# Planck-HUB.net
KiCad netlist of a schematic drawn in Altium Designer
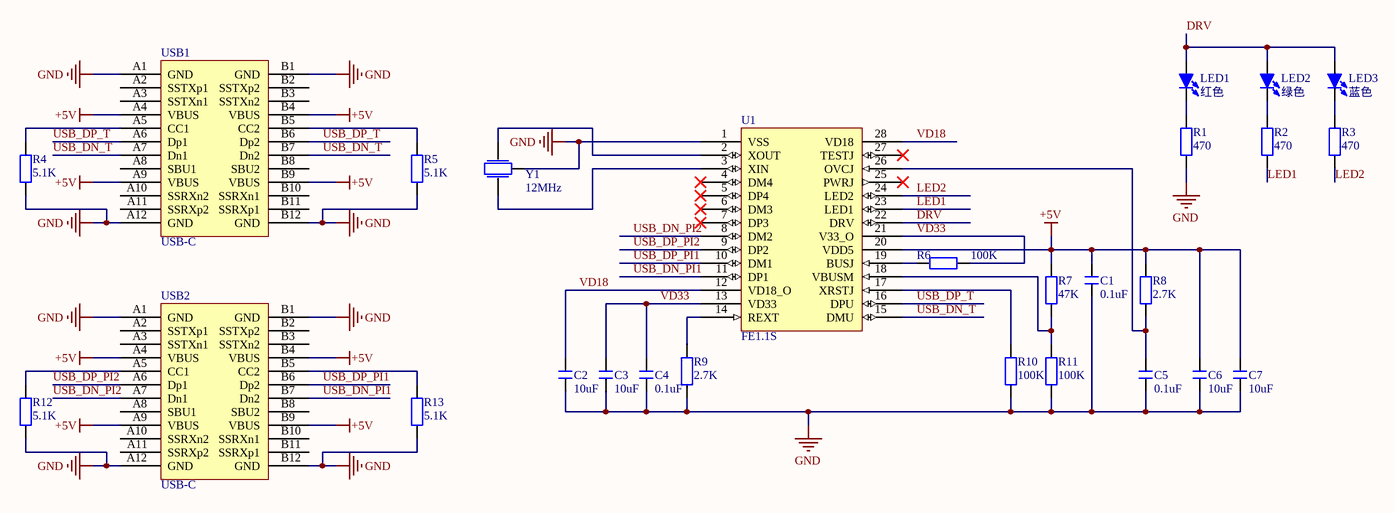
[diagram p0: Planck-HUB.SchDoc]

(export (version "E")
  (design (tool "Eeschema 10.0.6"))
  (components
    (comp (ref "C1")
      (value "0.1uF")
      (footprint "C 0402_L")
      (description "贴片电容")
      (libsource (lib "0.1 - 电阻-电容-电感") (part "C"))
    )
    (comp (ref "C2")
      (value "10uF")
      (footprint "C 0402_L")
      (description "贴片电容")
      (libsource (lib "0.1 - 电阻-电容-电感") (part "C"))
    )
    (comp (ref "C3")
      (value "10uF")
      (footprint "C 0402_L")
      (description "贴片电容")
      (libsource (lib "0.1 - 电阻-电容-电感") (part "C"))
    )
    (comp (ref "C4")
      (value "0.1uF")
      (footprint "C 0402_L")
      (description "贴片电容")
      (libsource (lib "0.1 - 电阻-电容-电感") (part "C"))
    )
    (comp (ref "C5")
      (value "0.1uF")
      (footprint "C 0402_L")
      (description "贴片电容")
      (libsource (lib "0.1 - 电阻-电容-电感") (part "C"))
    )
    (comp (ref "C6")
      (value "10uF")
      (footprint "C 0402_L")
      (description "贴片电容")
      (libsource (lib "0.1 - 电阻-电容-电感") (part "C"))
    )
    (comp (ref "C7")
      (value "10uF")
      (footprint "C 0402_L")
      (description "贴片电容")
      (libsource (lib "0.1 - 电阻-电容-电感") (part "C"))
    )
    (comp (ref "LED1")
      (value "红色")
      (footprint "LED_0402_RED")
      (description "贴片LED")
      (fields (field (name "版权归属") "封装库来自淘宝 ID：黄晶宝石"))
      (libsource (lib "0.3 - LED发光二极管") (part "LED-SMD"))
    )
    (comp (ref "LED2")
      (value "绿色")
      (footprint "LED_0402_RED")
      (description "贴片LED")
      (fields (field (name "版权归属") "封装库来自淘宝 ID：黄晶宝石"))
      (libsource (lib "0.3 - LED发光二极管") (part "LED-SMD"))
    )
    (comp (ref "LED3")
      (value "蓝色")
      (footprint "LED_0402_RED")
      (description "贴片LED")
      (fields (field (name "版权归属") "封装库来自淘宝 ID：黄晶宝石"))
      (libsource (lib "0.3 - LED发光二极管") (part "LED-SMD"))
    )
    (comp (ref "R1")
      (value "470")
      (footprint "R 0402_L")
      (description "贴片电阻")
      (fields (field (name "版权归属") "来自淘宝 ID：黄晶宝石"))
      (libsource (lib "0.1 - 电阻-电容-电感") (part "R"))
    )
    (comp (ref "R2")
      (value "470")
      (footprint "R 0402_L")
      (description "贴片电阻")
      (fields (field (name "版权归属") "来自淘宝 ID：黄晶宝石"))
      (libsource (lib "0.1 - 电阻-电容-电感") (part "R"))
    )
    (comp (ref "R3")
      (value "470")
      (footprint "R 0402_L")
      (description "贴片电阻")
      (fields (field (name "版权归属") "来自淘宝 ID：黄晶宝石"))
      (libsource (lib "0.1 - 电阻-电容-电感") (part "R"))
    )
    (comp (ref "R4")
      (value "5.1K")
      (footprint "R 0402_L")
      (description "贴片电阻")
      (fields (field (name "版权归属") "来自淘宝 ID：黄晶宝石"))
      (libsource (lib "0.1 - 电阻-电容-电感") (part "R"))
    )
    (comp (ref "R5")
      (value "5.1K")
      (footprint "R 0402_L")
      (description "贴片电阻")
      (fields (field (name "版权归属") "来自淘宝 ID：黄晶宝石"))
      (libsource (lib "0.1 - 电阻-电容-电感") (part "R"))
    )
    (comp (ref "R6")
      (value "100K")
      (footprint "R 0402_L")
      (description "贴片电阻")
      (fields (field (name "版权归属") "来自淘宝 ID：黄晶宝石"))
      (libsource (lib "0.1 - 电阻-电容-电感") (part "R"))
    )
    (comp (ref "R7")
      (value "47K")
      (footprint "R 0402_L")
      (description "贴片电阻")
      (fields (field (name "版权归属") "来自淘宝 ID：黄晶宝石"))
      (libsource (lib "0.1 - 电阻-电容-电感") (part "R"))
    )
    (comp (ref "R8")
      (value "2.7K")
      (footprint "R 0402_L")
      (description "贴片电阻")
      (fields (field (name "版权归属") "来自淘宝 ID：黄晶宝石"))
      (libsource (lib "0.1 - 电阻-电容-电感") (part "R"))
    )
    (comp (ref "R9")
      (value "2.7K")
      (footprint "R 0402_L")
      (description "贴片电阻")
      (fields (field (name "版权归属") "来自淘宝 ID：黄晶宝石"))
      (libsource (lib "0.1 - 电阻-电容-电感") (part "R"))
    )
    (comp (ref "R10")
      (value "100K")
      (footprint "R 0402_L")
      (description "贴片电阻")
      (fields (field (name "版权归属") "来自淘宝 ID：黄晶宝石"))
      (libsource (lib "0.1 - 电阻-电容-电感") (part "R"))
    )
    (comp (ref "R11")
      (value "100K")
      (footprint "R 0402_L")
      (description "贴片电阻")
      (fields (field (name "版权归属") "来自淘宝 ID：黄晶宝石"))
      (libsource (lib "0.1 - 电阻-电容-电感") (part "R"))
    )
    (comp (ref "R12")
      (value "5.1K")
      (footprint "R 0402_L")
      (description "贴片电阻")
      (fields (field (name "版权归属") "来自淘宝 ID：黄晶宝石"))
      (libsource (lib "0.1 - 电阻-电容-电感") (part "R"))
    )
    (comp (ref "R13")
      (value "5.1K")
      (footprint "R 0402_L")
      (description "贴片电阻")
      (fields (field (name "版权归属") "来自淘宝 ID：黄晶宝石"))
      (libsource (lib "0.1 - 电阻-电容-电感") (part "R"))
    )
    (comp (ref "U1")
      (value "FE1.1S")
      (footprint "SSOP28_L")
      (libsource (lib "自己建的库") (part "FE1.1S USB HUB"))
    )
    (comp (ref "USB1")
      (value "USB-C")
      (footprint "USB Type-C-16Pin_A")
      (description "USB-C型母接口")
      (fields (field (name "版权归属") "源创客"))
      (libsource (lib "接口类") (part "USB-C/S"))
    )
    (comp (ref "USB2")
      (value "USB-C")
      (footprint "USB-C-SMD_TYPE-C-31-G-01")
      (description "USB-C型母接口")
      (fields (field (name "版权归属") "源创客"))
      (libsource (lib "接口类") (part "USB-C/S"))
    )
    (comp (ref "Y1")
      (value "12MHz")
      (footprint "晶振-3P")
      (description "村田贴片")
      (libsource (lib "MyPcbLib") (part "晶振-3Pin"))
    )
  )
  (nets
    (net (code "1") (name "+5V") (class "Default")
      (node (ref "C1") (pin "2") (pinfunction "2_2") (pintype "passive"))
      (node (ref "C6") (pin "2") (pinfunction "2_2") (pintype "passive"))
      (node (ref "C7") (pin "2") (pinfunction "2_2") (pintype "passive"))
      (node (ref "R7") (pin "1") (pinfunction "1_1") (pintype "passive"))
      (node (ref "R8") (pin "1") (pinfunction "1_1") (pintype "passive"))
      (node (ref "U1") (pin "20") (pinfunction "VDD5_20") (pintype "power_in"))
      (node (ref "USB1") (pin "A4") (pinfunction "VBUS_A4") (pintype "passive"))
      (node (ref "USB1") (pin "A9") (pinfunction "VBUS_A9") (pintype "passive"))
      (node (ref "USB1") (pin "B4") (pinfunction "VBUS_B4") (pintype "passive"))
      (node (ref "USB1") (pin "B9") (pinfunction "VBUS_B9") (pintype "passive"))
      (node (ref "USB2") (pin "A4") (pinfunction "VBUS_A4") (pintype "passive"))
      (node (ref "USB2") (pin "A9") (pinfunction "VBUS_A9") (pintype "passive"))
      (node (ref "USB2") (pin "B4") (pinfunction "VBUS_B4") (pintype "passive"))
      (node (ref "USB2") (pin "B9") (pinfunction "VBUS_B9") (pintype "passive"))
    )
    (net (code "2") (name "/DRV") (class "Default")
      (node (ref "LED1") (pin "1") (pinfunction "A_1") (pintype "passive"))
      (node (ref "LED2") (pin "1") (pinfunction "A_1") (pintype "passive"))
      (node (ref "LED3") (pin "1") (pinfunction "A_1") (pintype "passive"))
      (node (ref "U1") (pin "22") (pinfunction "DRV_22") (pintype "bidirectional"))
    )
    (net (code "3") (name "/LED1") (class "Default")
      (node (ref "R2") (pin "1") (pinfunction "1_1") (pintype "passive"))
      (node (ref "U1") (pin "23") (pinfunction "LED1_23") (pintype "bidirectional"))
    )
    (net (code "4") (name "/LED2") (class "Default")
      (node (ref "R3") (pin "1") (pinfunction "1_1") (pintype "passive"))
      (node (ref "U1") (pin "24") (pinfunction "LED2_24") (pintype "bidirectional"))
    )
    (net (code "5") (name "/USB_DN_PI1") (class "Default")
      (node (ref "U1") (pin "11") (pinfunction "DP1_11") (pintype "bidirectional"))
      (node (ref "USB2") (pin "B7") (pinfunction "Dn2_B7") (pintype "passive"))
    )
    (net (code "6") (name "/USB_DN_PI2") (class "Default")
      (node (ref "U1") (pin "8") (pinfunction "DM2_8") (pintype "bidirectional"))
      (node (ref "USB2") (pin "A7") (pinfunction "Dn1_A7") (pintype "passive"))
    )
    (net (code "7") (name "/USB_DN_T") (class "Default")
      (node (ref "U1") (pin "15") (pinfunction "DMU_15") (pintype "bidirectional"))
      (node (ref "USB1") (pin "A7") (pinfunction "Dn1_A7") (pintype "passive"))
      (node (ref "USB1") (pin "B7") (pinfunction "Dn2_B7") (pintype "passive"))
    )
    (net (code "8") (name "/USB_DP_PI1") (class "Default")
      (node (ref "U1") (pin "10") (pinfunction "DM1_10") (pintype "bidirectional"))
      (node (ref "USB2") (pin "B6") (pinfunction "Dp2_B6") (pintype "passive"))
    )
    (net (code "9") (name "/USB_DP_PI2") (class "Default")
      (node (ref "U1") (pin "9") (pinfunction "DP2_9") (pintype "bidirectional"))
      (node (ref "USB2") (pin "A6") (pinfunction "Dp1_A6") (pintype "passive"))
    )
    (net (code "10") (name "/USB_DP_T") (class "Default")
      (node (ref "U1") (pin "16") (pinfunction "DPU_16") (pintype "bidirectional"))
      (node (ref "USB1") (pin "A6") (pinfunction "Dp1_A6") (pintype "passive"))
      (node (ref "USB1") (pin "B6") (pinfunction "Dp2_B6") (pintype "passive"))
    )
    (net (code "11") (name "/VD18") (class "Default")
      (node (ref "C2") (pin "1") (pinfunction "1_1") (pintype "passive"))
      (node (ref "U1") (pin "12") (pinfunction "VD18_O_12") (pintype "power_in"))
      (node (ref "U1") (pin "28") (pinfunction "VD18_28") (pintype "power_in"))
    )
    (net (code "12") (name "/VD33") (class "Default")
      (node (ref "C3") (pin "2") (pinfunction "2_2") (pintype "passive"))
      (node (ref "C4") (pin "2") (pinfunction "2_2") (pintype "passive"))
      (node (ref "R6") (pin "2") (pinfunction "2_2") (pintype "passive"))
      (node (ref "U1") (pin "13") (pinfunction "VD33_13") (pintype "power_in"))
      (node (ref "U1") (pin "21") (pinfunction "V33_O_21") (pintype "power_in"))
    )
    (net (code "13") (name "GND") (class "Default")
      (node (ref "C1") (pin "1") (pinfunction "1_1") (pintype "passive"))
      (node (ref "C2") (pin "2") (pinfunction "2_2") (pintype "passive"))
      (node (ref "C3") (pin "1") (pinfunction "1_1") (pintype "passive"))
      (node (ref "C4") (pin "1") (pinfunction "1_1") (pintype "passive"))
      (node (ref "C5") (pin "1") (pinfunction "1_1") (pintype "passive"))
      (node (ref "C6") (pin "1") (pinfunction "1_1") (pintype "passive"))
      (node (ref "C7") (pin "1") (pinfunction "1_1") (pintype "passive"))
      (node (ref "R1") (pin "1") (pinfunction "1_1") (pintype "passive"))
      (node (ref "R10") (pin "2") (pinfunction "2_2") (pintype "passive"))
      (node (ref "R11") (pin "2") (pinfunction "2_2") (pintype "passive"))
      (node (ref "R12") (pin "1") (pinfunction "1_1") (pintype "passive"))
      (node (ref "R13") (pin "1") (pinfunction "1_1") (pintype "passive"))
      (node (ref "R4") (pin "1") (pinfunction "1_1") (pintype "passive"))
      (node (ref "R5") (pin "1") (pinfunction "1_1") (pintype "passive"))
      (node (ref "R9") (pin "1") (pinfunction "1_1") (pintype "passive"))
      (node (ref "U1") (pin "1") (pinfunction "VSS_1") (pintype "power_in"))
      (node (ref "USB1") (pin "A1") (pinfunction "GND_A1") (pintype "passive"))
      (node (ref "USB1") (pin "A12") (pinfunction "GND_A12") (pintype "passive"))
      (node (ref "USB1") (pin "B1") (pinfunction "GND_B1") (pintype "passive"))
      (node (ref "USB1") (pin "B12") (pinfunction "GND_B12") (pintype "passive"))
      (node (ref "USB2") (pin "A1") (pinfunction "GND_A1") (pintype "passive"))
      (node (ref "USB2") (pin "A12") (pinfunction "GND_A12") (pintype "passive"))
      (node (ref "USB2") (pin "B1") (pinfunction "GND_B1") (pintype "passive"))
      (node (ref "USB2") (pin "B12") (pinfunction "GND_B12") (pintype "passive"))
      (node (ref "Y1") (pin "2") (pinfunction "2_2") (pintype "passive"))
    )
    (net (code "14") (name "Net-(LED1-K)") (class "Default")
      (node (ref "LED1") (pin "2") (pinfunction "K_2") (pintype "passive"))
      (node (ref "R1") (pin "2") (pinfunction "2_2") (pintype "passive"))
    )
    (net (code "15") (name "Net-(LED2-K)") (class "Default")
      (node (ref "LED2") (pin "2") (pinfunction "K_2") (pintype "passive"))
      (node (ref "R2") (pin "2") (pinfunction "2_2") (pintype "passive"))
    )
    (net (code "16") (name "Net-(LED3-K)") (class "Default")
      (node (ref "LED3") (pin "2") (pinfunction "K_2") (pintype "passive"))
      (node (ref "R3") (pin "2") (pinfunction "2_2") (pintype "passive"))
    )
    (net (code "17") (name "Net-(U1-BUSJ)") (class "Default")
      (node (ref "R6") (pin "1") (pinfunction "1_1") (pintype "passive"))
      (node (ref "U1") (pin "19") (pinfunction "BUSJ_19") (pintype "input"))
    )
    (net (code "18") (name "Net-(U1-OVCJ)") (class "Default")
      (node (ref "C5") (pin "2") (pinfunction "2_2") (pintype "passive"))
      (node (ref "R8") (pin "2") (pinfunction "2_2") (pintype "passive"))
      (node (ref "U1") (pin "26") (pinfunction "OVCJ_26") (pintype "input"))
    )
    (net (code "19") (name "Net-(U1-REXT)") (class "Default")
      (node (ref "R9") (pin "2") (pinfunction "2_2") (pintype "passive"))
      (node (ref "U1") (pin "14") (pinfunction "REXT_14") (pintype "input"))
    )
    (net (code "20") (name "Net-(U1-VBUSM)") (class "Default")
      (node (ref "R11") (pin "1") (pinfunction "1_1") (pintype "passive"))
      (node (ref "R7") (pin "2") (pinfunction "2_2") (pintype "passive"))
      (node (ref "U1") (pin "18") (pinfunction "VBUSM_18") (pintype "input"))
    )
    (net (code "21") (name "Net-(U1-XIN)") (class "Default")
      (node (ref "U1") (pin "3") (pinfunction "XIN_3") (pintype "bidirectional"))
      (node (ref "Y1") (pin "1") (pinfunction "1_1") (pintype "passive"))
    )
    (net (code "22") (name "Net-(U1-XOUT)") (class "Default")
      (node (ref "U1") (pin "2") (pinfunction "XOUT_2") (pintype "bidirectional"))
      (node (ref "Y1") (pin "3") (pinfunction "3_3") (pintype "passive"))
    )
    (net (code "23") (name "Net-(U1-XRSTJ)") (class "Default")
      (node (ref "R10") (pin "1") (pinfunction "1_1") (pintype "passive"))
      (node (ref "U1") (pin "17") (pinfunction "XRSTJ_17") (pintype "input"))
    )
    (net (code "24") (name "Net-(USB1-CC1)") (class "Default")
      (node (ref "R4") (pin "2") (pinfunction "2_2") (pintype "passive"))
      (node (ref "USB1") (pin "A5") (pinfunction "CC1_A5") (pintype "passive"))
    )
    (net (code "25") (name "Net-(USB1-CC2)") (class "Default")
      (node (ref "R5") (pin "2") (pinfunction "2_2") (pintype "passive"))
      (node (ref "USB1") (pin "B5") (pinfunction "CC2_B5") (pintype "passive"))
    )
    (net (code "26") (name "Net-(USB2-CC1)") (class "Default")
      (node (ref "R12") (pin "2") (pinfunction "2_2") (pintype "passive"))
      (node (ref "USB2") (pin "A5") (pinfunction "CC1_A5") (pintype "passive"))
    )
    (net (code "27") (name "Net-(USB2-CC2)") (class "Default")
      (node (ref "R13") (pin "2") (pinfunction "2_2") (pintype "passive"))
      (node (ref "USB2") (pin "B5") (pinfunction "CC2_B5") (pintype "passive"))
    )
    (net (code "28") (name "unconnected-(U1-DM3-Pad6)") (class "Default")
      (node (ref "U1") (pin "6") (pinfunction "DM3_6") (pintype "bidirectional+no_connect"))
    )
    (net (code "29") (name "unconnected-(U1-DM4-Pad4)") (class "Default")
      (node (ref "U1") (pin "4") (pinfunction "DM4_4") (pintype "bidirectional+no_connect"))
    )
    (net (code "30") (name "unconnected-(U1-DP3-Pad7)") (class "Default")
      (node (ref "U1") (pin "7") (pinfunction "DP3_7") (pintype "bidirectional+no_connect"))
    )
    (net (code "31") (name "unconnected-(U1-DP4-Pad5)") (class "Default")
      (node (ref "U1") (pin "5") (pinfunction "DP4_5") (pintype "bidirectional+no_connect"))
    )
    (net (code "32") (name "unconnected-(U1-PWRJ-Pad25)") (class "Default")
      (node (ref "U1") (pin "25") (pinfunction "PWRJ_25") (pintype "output+no_connect"))
    )
    (net (code "33") (name "unconnected-(U1-TESTJ-Pad27)") (class "Default")
      (node (ref "U1") (pin "27") (pinfunction "TESTJ_27") (pintype "bidirectional+no_connect"))
    )
    (net (code "34") (name "unconnected-(USB1-SBU1-PadA8)") (class "Default")
      (node (ref "USB1") (pin "A8") (pinfunction "SBU1_A8") (pintype "passive"))
    )
    (net (code "35") (name "unconnected-(USB1-SBU2-PadB8)") (class "Default")
      (node (ref "USB1") (pin "B8") (pinfunction "SBU2_B8") (pintype "passive"))
    )
    (net (code "36") (name "unconnected-(USB1-SSRXn1-PadB10)") (class "Default")
      (node (ref "USB1") (pin "B10") (pinfunction "SSRXn1_B10") (pintype "passive"))
    )
    (net (code "37") (name "unconnected-(USB1-SSRXn2-PadA10)") (class "Default")
      (node (ref "USB1") (pin "A10") (pinfunction "SSRXn2_A10") (pintype "passive"))
    )
    (net (code "38") (name "unconnected-(USB1-SSRXp1-PadB11)") (class "Default")
      (node (ref "USB1") (pin "B11") (pinfunction "SSRXp1_B11") (pintype "passive"))
    )
    (net (code "39") (name "unconnected-(USB1-SSRXp2-PadA11)") (class "Default")
      (node (ref "USB1") (pin "A11") (pinfunction "SSRXp2_A11") (pintype "passive"))
    )
    (net (code "40") (name "unconnected-(USB1-SSTXn1-PadA3)") (class "Default")
      (node (ref "USB1") (pin "A3") (pinfunction "SSTXn1_A3") (pintype "passive"))
    )
    (net (code "41") (name "unconnected-(USB1-SSTXn2-PadB3)") (class "Default")
      (node (ref "USB1") (pin "B3") (pinfunction "SSTXn2_B3") (pintype "passive"))
    )
    (net (code "42") (name "unconnected-(USB1-SSTXp1-PadA2)") (class "Default")
      (node (ref "USB1") (pin "A2") (pinfunction "SSTXp1_A2") (pintype "passive"))
    )
    (net (code "43") (name "unconnected-(USB1-SSTXp2-PadB2)") (class "Default")
      (node (ref "USB1") (pin "B2") (pinfunction "SSTXp2_B2") (pintype "passive"))
    )
    (net (code "44") (name "unconnected-(USB2-SBU1-PadA8)") (class "Default")
      (node (ref "USB2") (pin "A8") (pinfunction "SBU1_A8") (pintype "passive"))
    )
    (net (code "45") (name "unconnected-(USB2-SBU2-PadB8)") (class "Default")
      (node (ref "USB2") (pin "B8") (pinfunction "SBU2_B8") (pintype "passive"))
    )
    (net (code "46") (name "unconnected-(USB2-SSRXn1-PadB10)") (class "Default")
      (node (ref "USB2") (pin "B10") (pinfunction "SSRXn1_B10") (pintype "passive"))
    )
    (net (code "47") (name "unconnected-(USB2-SSRXn2-PadA10)") (class "Default")
      (node (ref "USB2") (pin "A10") (pinfunction "SSRXn2_A10") (pintype "passive"))
    )
    (net (code "48") (name "unconnected-(USB2-SSRXp1-PadB11)") (class "Default")
      (node (ref "USB2") (pin "B11") (pinfunction "SSRXp1_B11") (pintype "passive"))
    )
    (net (code "49") (name "unconnected-(USB2-SSRXp2-PadA11)") (class "Default")
      (node (ref "USB2") (pin "A11") (pinfunction "SSRXp2_A11") (pintype "passive"))
    )
    (net (code "50") (name "unconnected-(USB2-SSTXn1-PadA3)") (class "Default")
      (node (ref "USB2") (pin "A3") (pinfunction "SSTXn1_A3") (pintype "passive"))
    )
    (net (code "51") (name "unconnected-(USB2-SSTXn2-PadB3)") (class "Default")
      (node (ref "USB2") (pin "B3") (pinfunction "SSTXn2_B3") (pintype "passive"))
    )
    (net (code "52") (name "unconnected-(USB2-SSTXp1-PadA2)") (class "Default")
      (node (ref "USB2") (pin "A2") (pinfunction "SSTXp1_A2") (pintype "passive"))
    )
    (net (code "53") (name "unconnected-(USB2-SSTXp2-PadB2)") (class "Default")
      (node (ref "USB2") (pin "B2") (pinfunction "SSTXp2_B2") (pintype "passive"))
    )
  )
)
